# Uart.net
KiCad netlist of a schematic drawn in Altium Designer
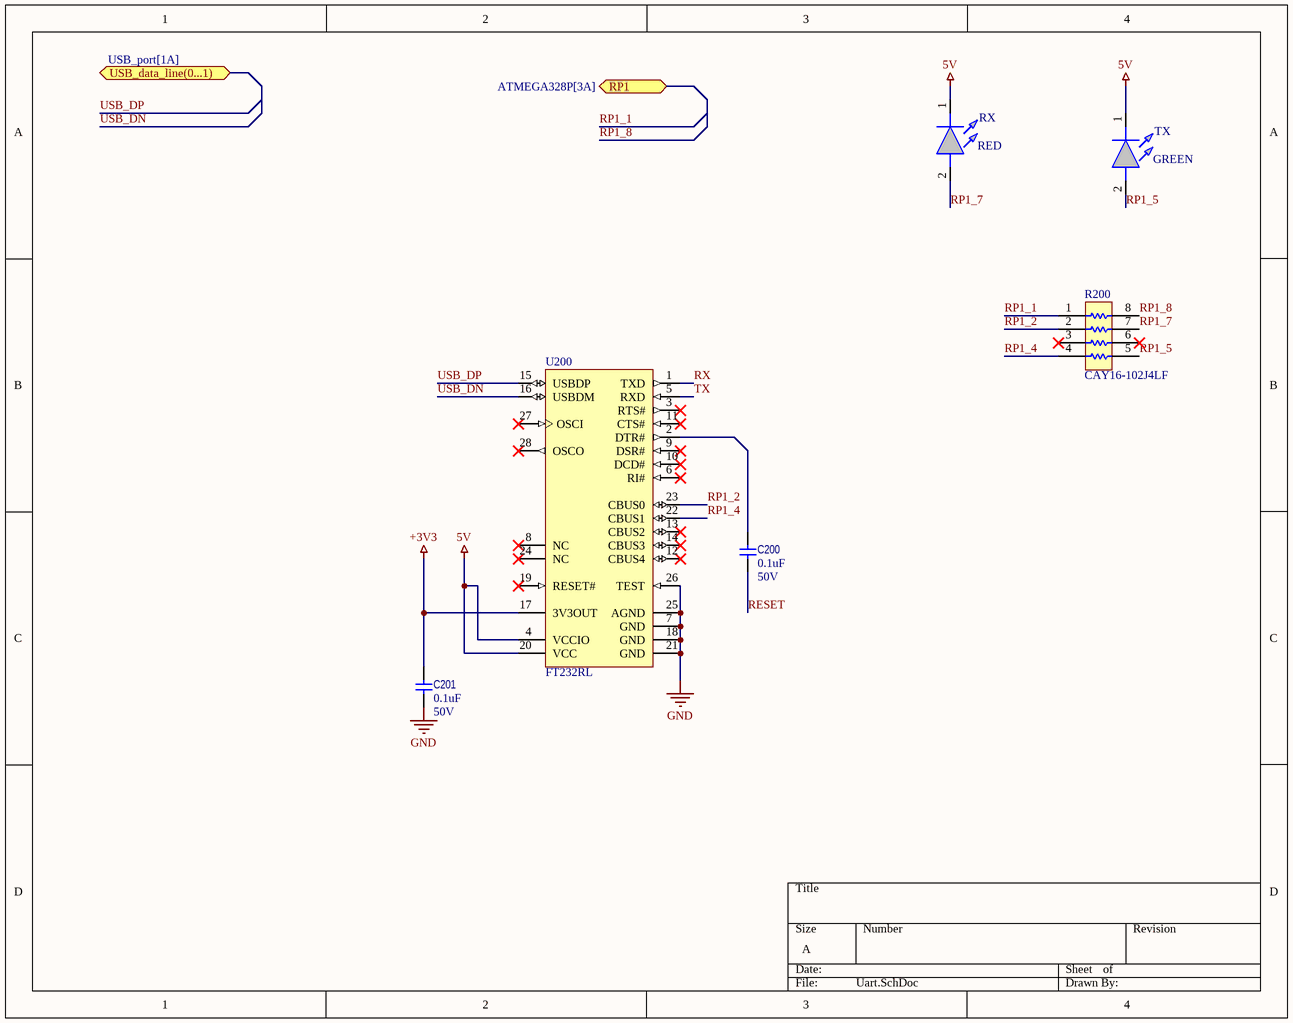
[diagram p0: Uart.SchDoc]

(export (version "E")
  (design (tool "Eeschema 10.0.6"))
  (components
    (comp (ref "C200")
      (value "0.1uF")
      (footprint "CAPC1005X55N")
      (description "CAP CER 0.1uF ±10% 50V X7R 0603 (1608 Metric)")
      (fields
        (field (name "VOLTAGE_RATING") "50V")
        (field (name "MANUFACTURER PART NUMBER") "C0603C104K5RECAUTO")
        (field (name "MANUFACTURER") "KEMET")
        (field (name "CREATED BY") "randy")
        (field (name "UPDATED BY") "randy")
      )
      (libsource (lib "Parts") (part "CAP_NOPOL"))
    )
    (comp (ref "C201")
      (value "0.1uF")
      (footprint "CAPC1005X55N")
      (description "CAP CER 0.1uF ±10% 50V X7R 0603 (1608 Metric)")
      (fields
        (field (name "VOLTAGE_RATING") "50V")
        (field (name "MANUFACTURER PART NUMBER") "C0603C104K5RECAUTO")
        (field (name "MANUFACTURER") "KEMET")
        (field (name "CREATED BY") "randy")
        (field (name "UPDATED BY") "randy")
      )
      (libsource (lib "Parts") (part "CAP_NOPOL"))
    )
    (comp (ref "R200")
      (value "CAY16-102J4LF")
      (footprint "BOUR-CAY16-J4_V")
      (description "Chip Resistor Array, 1 KOhm, +/- 5%, 62.5 mW, -55 to 125 degC, 8-Pin SMD, RoHS, Tape and Reel")
      (fields (field (name "TOLERANCE") "1%"))
      (libsource (lib "Altium Content Vault") (part "RES-P-8"))
    )
    (comp (ref "RX")
      (value "KPT-2012YC")
      (footprint "LEDC2012X75N")
      (description "Kingbright KPT-2012YC Yellow LED, 588 nm, 2012 (0805), Rectangle Lens SMD Package")
      (fields (field (name "COLOR") "RED"))
      (libsource (lib "KPT-2012YC") (part "KPT-2012YC"))
    )
    (comp (ref "TX")
      (value "KPT-2012YC")
      (footprint "LEDC2012X75N")
      (description "Kingbright KPT-2012YC Yellow LED, 588 nm, 2012 (0805), Rectangle Lens SMD Package")
      (fields (field (name "COLOR") "GREEN"))
      (libsource (lib "KPT-2012YC") (part "KPT-2012YC"))
    )
    (comp (ref "U200")
      (value "FT232RL")
      (footprint "FTDI-SSOP-28_M")
      (description "IC USB FS SERIAL UART 28-SSOP")
      (fields (field (name "MANUFACTURER") "FTDI"))
      (libsource (lib "Altium Content Vault") (part "FTDI-FT232-SSOP-28"))
    )
  )
  (nets
    (net (code "1") (name "+3V3") (class "Default")
      (node (ref "C201") (pin "1") (pinfunction "1_1") (pintype "passive"))
      (node (ref "U200") (pin "17") (pinfunction "3V3OUT_17") (pintype "power_in"))
    )
    (net (code "2") (name "/RESET") (class "Default")
      (node (ref "C200") (pin "2") (pinfunction "2_2") (pintype "passive"))
    )
    (net (code "4") (name "/RP1_1") (class "Default")
      (node (ref "R200") (pin "1") (pinfunction "1_1") (pintype "passive"))
    )
    (net (code "5") (name "/RP1_2") (class "Default")
      (node (ref "R200") (pin "2") (pinfunction "2_2") (pintype "passive"))
      (node (ref "U200") (pin "23") (pinfunction "CBUS0_23") (pintype "bidirectional"))
    )
    (net (code "6") (name "/RP1_4") (class "Default")
      (node (ref "R200") (pin "4") (pinfunction "4_4") (pintype "passive"))
      (node (ref "U200") (pin "22") (pinfunction "CBUS1_22") (pintype "bidirectional"))
    )
    (net (code "7") (name "/RP1_5") (class "Default")
      (node (ref "R200") (pin "5") (pinfunction "5_5") (pintype "passive"))
      (node (ref "TX") (pin "2") (pinfunction "A_2") (pintype "passive"))
    )
    (net (code "8") (name "/RP1_7") (class "Default")
      (node (ref "R200") (pin "7") (pinfunction "7_7") (pintype "passive"))
      (node (ref "RX") (pin "2") (pinfunction "A_2") (pintype "passive"))
    )
    (net (code "9") (name "/RP1_8") (class "Default")
      (node (ref "R200") (pin "8") (pinfunction "8_8") (pintype "passive"))
    )
    (net (code "10") (name "/RX") (class "Default")
      (node (ref "U200") (pin "1") (pinfunction "TXD_1") (pintype "output"))
    )
    (net (code "11") (name "/TX") (class "Default")
      (node (ref "U200") (pin "5") (pinfunction "RXD_5") (pintype "input"))
    )
    (net (code "12") (name "/USB_DN") (class "Default")
      (node (ref "U200") (pin "16") (pinfunction "USBDM_16") (pintype "bidirectional"))
    )
    (net (code "13") (name "/USB_DP") (class "Default")
      (node (ref "U200") (pin "15") (pinfunction "USBDP_15") (pintype "bidirectional"))
    )
    (net (code "15") (name "5V") (class "Default")
      (node (ref "RX") (pin "1") (pinfunction "K_1") (pintype "passive"))
      (node (ref "TX") (pin "1") (pinfunction "K_1") (pintype "passive"))
      (node (ref "U200") (pin "20") (pinfunction "VCC_20") (pintype "power_in"))
      (node (ref "U200") (pin "4") (pinfunction "VCCIO_4") (pintype "power_in"))
    )
    (net (code "16") (name "GND") (class "Default")
      (node (ref "C201") (pin "2") (pinfunction "2_2") (pintype "passive"))
      (node (ref "U200") (pin "18") (pinfunction "GND_18") (pintype "power_in"))
      (node (ref "U200") (pin "21") (pinfunction "GND_21") (pintype "power_in"))
      (node (ref "U200") (pin "25") (pinfunction "AGND_25") (pintype "power_in"))
      (node (ref "U200") (pin "26") (pinfunction "TEST_26") (pintype "input"))
      (node (ref "U200") (pin "7") (pinfunction "GND_7") (pintype "power_in"))
    )
    (net (code "17") (name "Net-(U200-DTR#)") (class "Default")
      (node (ref "C200") (pin "1") (pinfunction "1_1") (pintype "passive"))
      (node (ref "U200") (pin "2") (pinfunction "DTR#_2") (pintype "output"))
    )
    (net (code "18") (name "unconnected-(R200-Pad3)") (class "Default")
      (node (ref "R200") (pin "3") (pinfunction "3_3") (pintype "passive+no_connect"))
    )
    (net (code "19") (name "unconnected-(R200-Pad6)") (class "Default")
      (node (ref "R200") (pin "6") (pinfunction "6_6") (pintype "passive+no_connect"))
    )
    (net (code "20") (name "unconnected-(U200-CBUS2-Pad13)") (class "Default")
      (node (ref "U200") (pin "13") (pinfunction "CBUS2_13") (pintype "bidirectional+no_connect"))
    )
    (net (code "21") (name "unconnected-(U200-CBUS3-Pad14)") (class "Default")
      (node (ref "U200") (pin "14") (pinfunction "CBUS3_14") (pintype "bidirectional+no_connect"))
    )
    (net (code "22") (name "unconnected-(U200-CBUS4-Pad12)") (class "Default")
      (node (ref "U200") (pin "12") (pinfunction "CBUS4_12") (pintype "bidirectional+no_connect"))
    )
    (net (code "23") (name "unconnected-(U200-CTS#-Pad11)") (class "Default")
      (node (ref "U200") (pin "11") (pinfunction "CTS#_11") (pintype "input+no_connect"))
    )
    (net (code "24") (name "unconnected-(U200-DCD#-Pad10)") (class "Default")
      (node (ref "U200") (pin "10") (pinfunction "DCD#_10") (pintype "input+no_connect"))
    )
    (net (code "25") (name "unconnected-(U200-DSR#-Pad9)") (class "Default")
      (node (ref "U200") (pin "9") (pinfunction "DSR#_9") (pintype "input+no_connect"))
    )
    (net (code "26") (name "unconnected-(U200-NC-Pad8)") (class "Default")
      (node (ref "U200") (pin "8") (pinfunction "NC_8") (pintype "passive+no_connect"))
    )
    (net (code "27") (name "unconnected-(U200-NC-Pad24)") (class "Default")
      (node (ref "U200") (pin "24") (pinfunction "NC_24") (pintype "passive+no_connect"))
    )
    (net (code "28") (name "unconnected-(U200-OSCI-Pad27)") (class "Default")
      (node (ref "U200") (pin "27") (pinfunction "OSCI_27") (pintype "input+no_connect"))
    )
    (net (code "29") (name "unconnected-(U200-OSCO-Pad28)") (class "Default")
      (node (ref "U200") (pin "28") (pinfunction "OSCO_28") (pintype "output+no_connect"))
    )
    (net (code "30") (name "unconnected-(U200-RESET#-Pad19)") (class "Default")
      (node (ref "U200") (pin "19") (pinfunction "RESET#_19") (pintype "input+no_connect"))
    )
    (net (code "31") (name "unconnected-(U200-RI#-Pad6)") (class "Default")
      (node (ref "U200") (pin "6") (pinfunction "RI#_6") (pintype "input+no_connect"))
    )
    (net (code "32") (name "unconnected-(U200-RTS#-Pad3)") (class "Default")
      (node (ref "U200") (pin "3") (pinfunction "RTS#_3") (pintype "output+no_connect"))
    )
  )
)
